# FPGA.net
KiCad netlist of a schematic drawn in Altium Designer
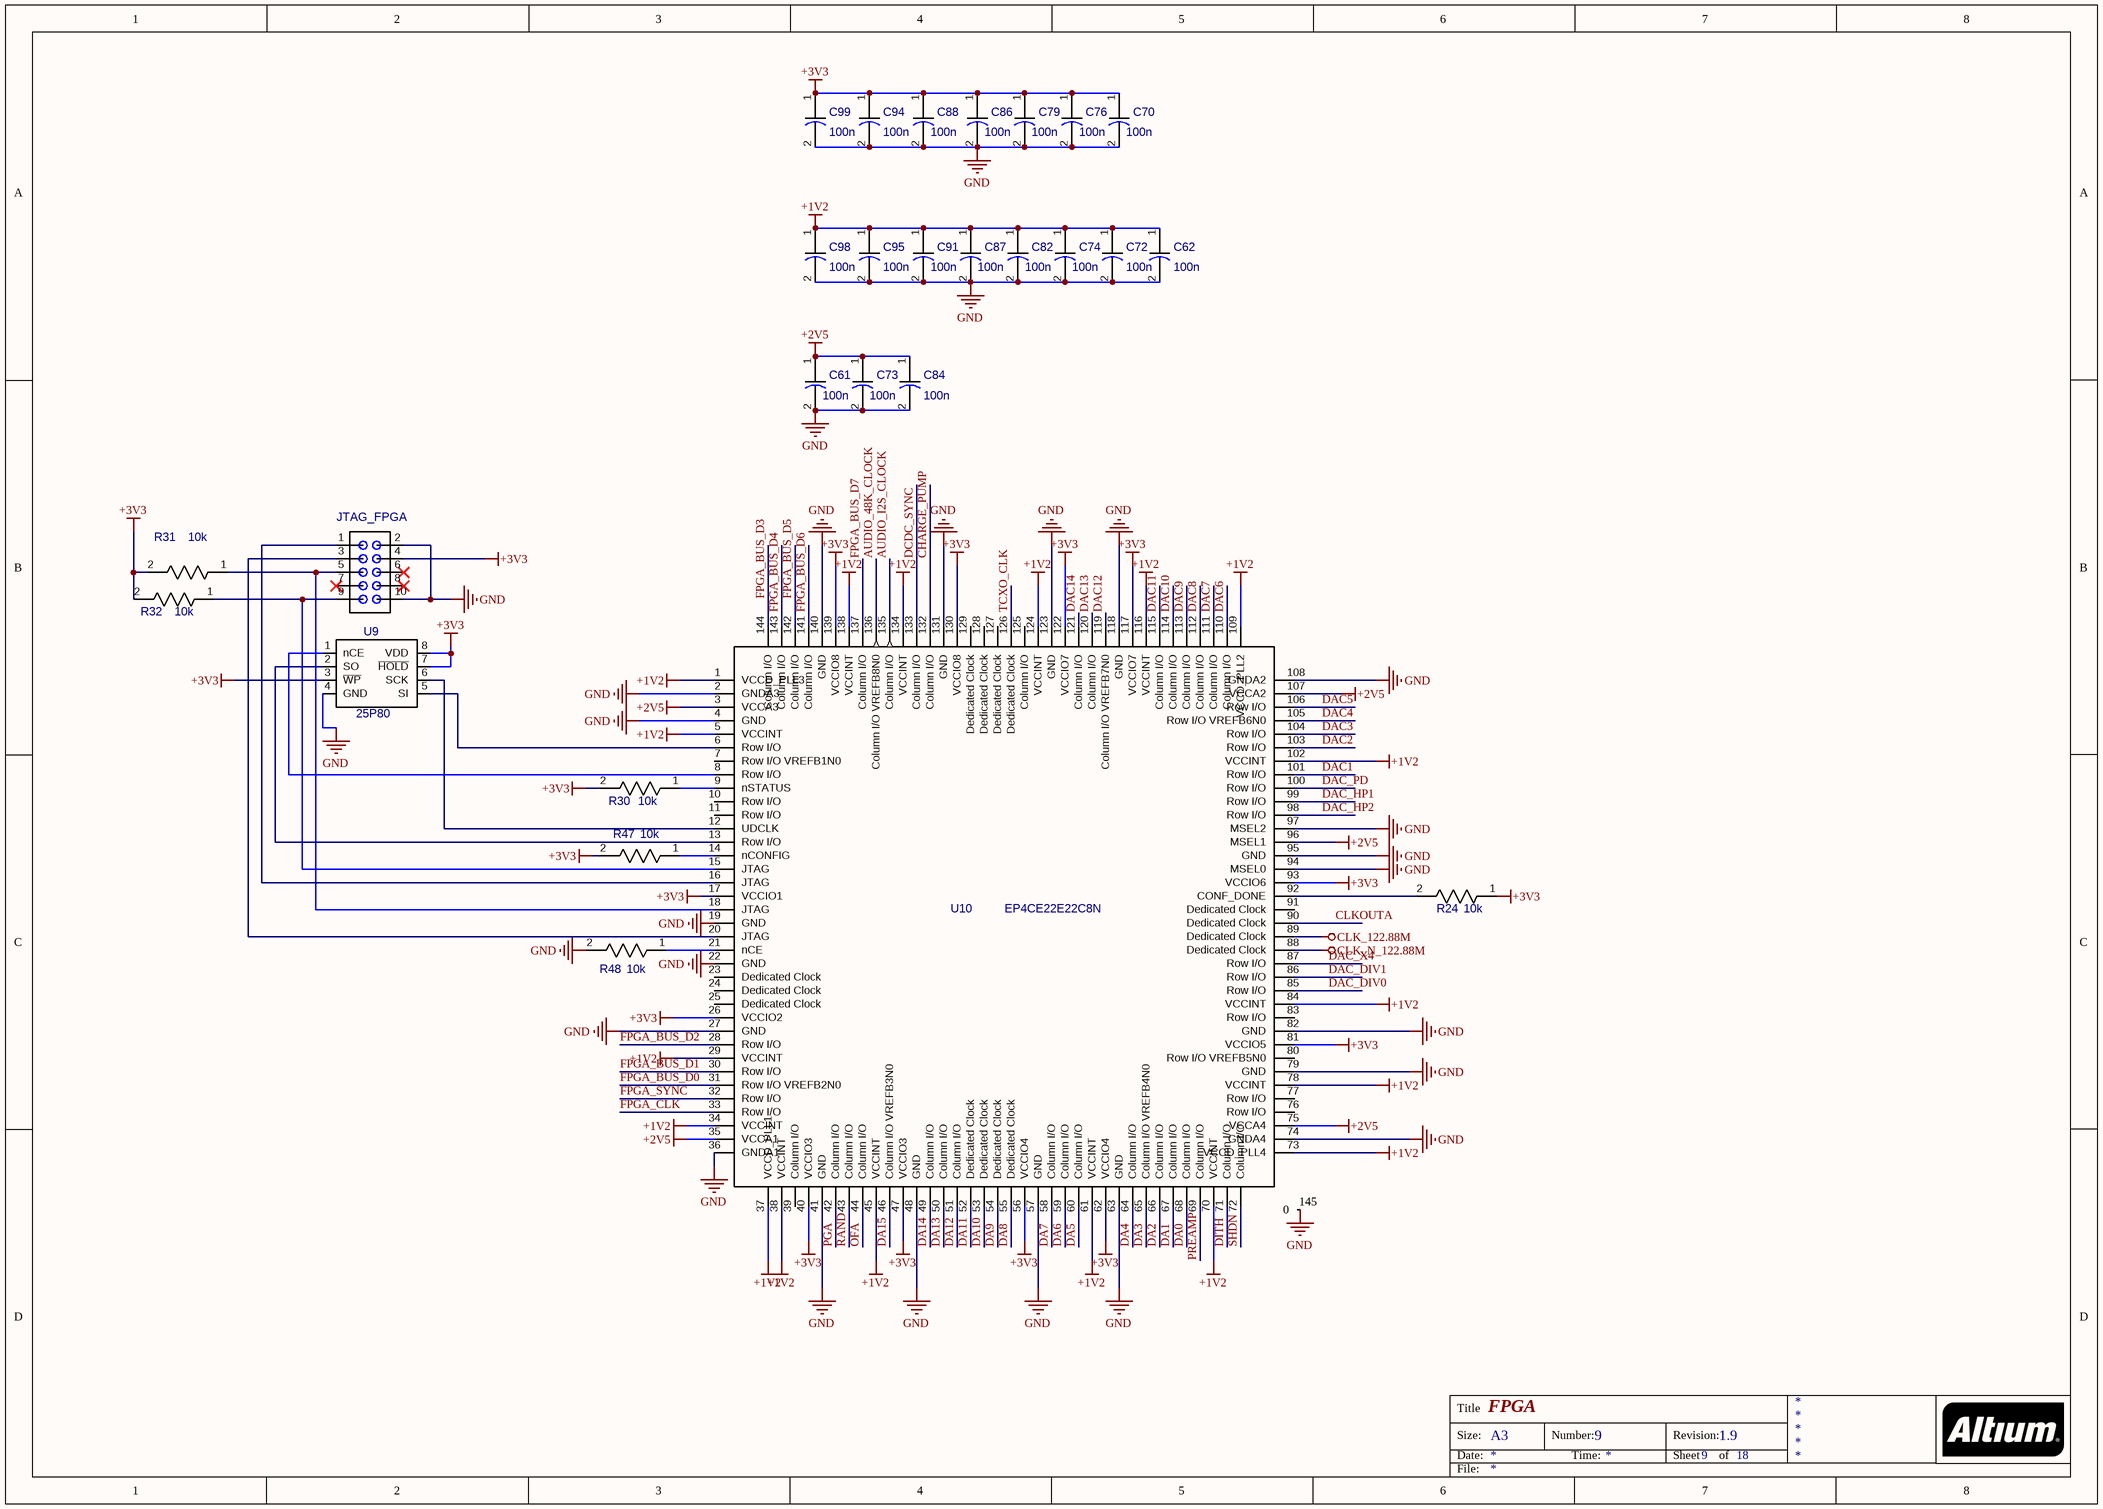
[diagram p0: FPGA.SchDoc]

(export (version "E")
  (design (tool "Eeschema 10.0.6"))
  (components
    (comp (ref "C61")
      (value "100n")
      (footprint "CAP_0805")
      (description "CAP_0805")
      (libsource (lib "*") (part "CAP_0805"))
    )
    (comp (ref "C62")
      (value "100n")
      (footprint "CAP_0805")
      (description "CAP_0805")
      (libsource (lib "*") (part "CAP_0805"))
    )
    (comp (ref "C70")
      (value "100n")
      (footprint "CAP_0805")
      (description "CAP_0805")
      (libsource (lib "*") (part "CAP_0805"))
    )
    (comp (ref "C72")
      (value "100n")
      (footprint "CAP_0805")
      (description "CAP_0805")
      (libsource (lib "*") (part "CAP_0805"))
    )
    (comp (ref "C73")
      (value "100n")
      (footprint "CAP_0805")
      (description "CAP_0805")
      (libsource (lib "*") (part "CAP_0805"))
    )
    (comp (ref "C74")
      (value "100n")
      (footprint "CAP_0805")
      (description "CAP_0805")
      (libsource (lib "*") (part "CAP_0805"))
    )
    (comp (ref "C76")
      (value "100n")
      (footprint "CAP_0805")
      (description "CAP_0805")
      (libsource (lib "*") (part "CAP_0805"))
    )
    (comp (ref "C79")
      (value "100n")
      (footprint "CAP_0805")
      (description "CAP_0805")
      (libsource (lib "*") (part "CAP_0805"))
    )
    (comp (ref "C82")
      (value "100n")
      (footprint "CAP_0805")
      (description "CAP_0805")
      (libsource (lib "*") (part "CAP_0805"))
    )
    (comp (ref "C84")
      (value "100n")
      (footprint "CAP_0805")
      (description "CAP_0805")
      (libsource (lib "*") (part "CAP_0805"))
    )
    (comp (ref "C86")
      (value "100n")
      (footprint "CAP_0805")
      (description "CAP_0805")
      (libsource (lib "*") (part "CAP_0805"))
    )
    (comp (ref "C87")
      (value "100n")
      (footprint "CAP_0805")
      (description "CAP_0805")
      (libsource (lib "*") (part "CAP_0805"))
    )
    (comp (ref "C88")
      (value "100n")
      (footprint "CAP_0805")
      (description "CAP_0805")
      (libsource (lib "*") (part "CAP_0805"))
    )
    (comp (ref "C91")
      (value "100n")
      (footprint "CAP_0805")
      (description "CAP_0805")
      (libsource (lib "*") (part "CAP_0805"))
    )
    (comp (ref "C94")
      (value "100n")
      (footprint "CAP_0805")
      (description "CAP_0805")
      (libsource (lib "*") (part "CAP_0805"))
    )
    (comp (ref "C95")
      (value "100n")
      (footprint "CAP_0805")
      (description "CAP_0805")
      (libsource (lib "*") (part "CAP_0805"))
    )
    (comp (ref "C98")
      (value "100n")
      (footprint "CAP_0805")
      (description "CAP_0805")
      (libsource (lib "*") (part "CAP_0805"))
    )
    (comp (ref "C99")
      (value "100n")
      (footprint "CAP_0805")
      (description "CAP_0805")
      (libsource (lib "*") (part "CAP_0805"))
    )
    (comp (ref "JTAG_FPGA")
      (value "~")
      (footprint "IDC10")
      (description "IDC10")
      (libsource (lib "*") (part "IDC10"))
    )
    (comp (ref "R24")
      (value "10k")
      (footprint "RES_0805")
      (description "RES_0805")
      (libsource (lib "*") (part "RES_0805"))
    )
    (comp (ref "R30")
      (value "10k")
      (footprint "RES_0805")
      (description "RES_0805")
      (libsource (lib "*") (part "RES_0805"))
    )
    (comp (ref "R31")
      (value "10k")
      (footprint "RES_0805")
      (description "RES_0805")
      (libsource (lib "*") (part "RES_0805"))
    )
    (comp (ref "R32")
      (value "10k")
      (footprint "RES_0805")
      (description "RES_0805")
      (libsource (lib "*") (part "RES_0805"))
    )
    (comp (ref "R47")
      (value "10k")
      (footprint "RES_0805")
      (description "RES_0805")
      (libsource (lib "*") (part "RES_0805"))
    )
    (comp (ref "R48")
      (value "10k")
      (footprint "RES_0805")
      (description "RES_0805")
      (libsource (lib "*") (part "RES_0805"))
    )
    (comp (ref "U9") (value "25P80") (footprint "25P80") (libsource (lib "*") (part "25P80")))
    (comp (ref "U10")
      (value "EP4CE22E22C8N")
      (footprint "QFP144-20-2222A")
      (libsource (lib "*") (part "EP4CE22E22C8N"))
    )
  )
  (nets
    (net (code "1") (name "+1V2") (class "Default")
      (node (ref "C62") (pin "1") (pinfunction "1_1") (pintype "passive"))
      (node (ref "C72") (pin "1") (pinfunction "1_1") (pintype "passive"))
      (node (ref "C74") (pin "1") (pinfunction "1_1") (pintype "passive"))
      (node (ref "C82") (pin "1") (pinfunction "1_1") (pintype "passive"))
      (node (ref "C87") (pin "1") (pinfunction "1_1") (pintype "passive"))
      (node (ref "C91") (pin "1") (pinfunction "1_1") (pintype "passive"))
      (node (ref "C95") (pin "1") (pinfunction "1_1") (pintype "passive"))
      (node (ref "C98") (pin "1") (pinfunction "1_1") (pintype "passive"))
      (node (ref "U10") (pin "1") (pinfunction "VCCD_PLL3_1") (pintype "passive"))
      (node (ref "U10") (pin "102") (pinfunction "VCCINT_102") (pintype "passive"))
      (node (ref "U10") (pin "109") (pinfunction "VCCD_PLL2_109") (pintype "passive"))
      (node (ref "U10") (pin "116") (pinfunction "VCCINT_116") (pintype "passive"))
      (node (ref "U10") (pin "124") (pinfunction "VCCINT_124") (pintype "passive"))
      (node (ref "U10") (pin "134") (pinfunction "VCCINT_134") (pintype "passive"))
      (node (ref "U10") (pin "138") (pinfunction "VCCINT_138") (pintype "passive"))
      (node (ref "U10") (pin "29") (pinfunction "VCCINT_29") (pintype "passive"))
      (node (ref "U10") (pin "34") (pinfunction "VCCINT_34") (pintype "passive"))
      (node (ref "U10") (pin "37") (pinfunction "VCCD_PLL1_37") (pintype "passive"))
      (node (ref "U10") (pin "38") (pinfunction "VCCINT_38") (pintype "passive"))
      (node (ref "U10") (pin "45") (pinfunction "VCCINT_45") (pintype "passive"))
      (node (ref "U10") (pin "5") (pinfunction "VCCINT_5") (pintype "passive"))
      (node (ref "U10") (pin "61") (pinfunction "VCCINT_61") (pintype "passive"))
      (node (ref "U10") (pin "70") (pinfunction "VCCINT_70") (pintype "passive"))
      (node (ref "U10") (pin "73") (pinfunction "VCCD_PLL4_73") (pintype "passive"))
      (node (ref "U10") (pin "78") (pinfunction "VCCINT_78") (pintype "passive"))
      (node (ref "U10") (pin "84") (pinfunction "VCCINT_84") (pintype "passive"))
    )
    (net (code "2") (name "+2V5") (class "Default")
      (node (ref "C61") (pin "1") (pinfunction "1_1") (pintype "passive"))
      (node (ref "C73") (pin "1") (pinfunction "1_1") (pintype "passive"))
      (node (ref "C84") (pin "1") (pinfunction "1_1") (pintype "passive"))
      (node (ref "U10") (pin "107") (pinfunction "VCCA2_107") (pintype "passive"))
      (node (ref "U10") (pin "3") (pinfunction "VCCA3_3") (pintype "passive"))
      (node (ref "U10") (pin "35") (pinfunction "VCCA1_35") (pintype "passive"))
      (node (ref "U10") (pin "75") (pinfunction "VCCA4_75") (pintype "passive"))
      (node (ref "U10") (pin "96") (pinfunction "MSEL1_96") (pintype "passive"))
    )
    (net (code "3") (name "+3V3") (class "Default")
      (node (ref "C70") (pin "1") (pinfunction "1_1") (pintype "passive"))
      (node (ref "C76") (pin "1") (pinfunction "1_1") (pintype "passive"))
      (node (ref "C79") (pin "1") (pinfunction "1_1") (pintype "passive"))
      (node (ref "C86") (pin "1") (pinfunction "1_1") (pintype "passive"))
      (node (ref "C88") (pin "1") (pinfunction "1_1") (pintype "passive"))
      (node (ref "C94") (pin "1") (pinfunction "1_1") (pintype "passive"))
      (node (ref "C99") (pin "1") (pinfunction "1_1") (pintype "passive"))
      (node (ref "JTAG_FPGA") (pin "4") (pinfunction "4_4") (pintype "passive"))
      (node (ref "R24") (pin "1") (pinfunction "1_1") (pintype "passive"))
      (node (ref "R30") (pin "2") (pinfunction "2_2") (pintype "passive"))
      (node (ref "R31") (pin "2") (pinfunction "2_2") (pintype "passive"))
      (node (ref "R32") (pin "2") (pinfunction "2_2") (pintype "passive"))
      (node (ref "R47") (pin "2") (pinfunction "2_2") (pintype "passive"))
      (node (ref "U10") (pin "117") (pinfunction "VCCIO7_117") (pintype "passive"))
      (node (ref "U10") (pin "122") (pinfunction "VCCIO7_122") (pintype "passive"))
      (node (ref "U10") (pin "130") (pinfunction "VCCIO8_130") (pintype "passive"))
      (node (ref "U10") (pin "139") (pinfunction "VCCIO8_139") (pintype "passive"))
      (node (ref "U10") (pin "17") (pinfunction "VCCIO1_17") (pintype "passive"))
      (node (ref "U10") (pin "26") (pinfunction "VCCIO2_26") (pintype "passive"))
      (node (ref "U10") (pin "40") (pinfunction "VCCIO3_40") (pintype "passive"))
      (node (ref "U10") (pin "47") (pinfunction "VCCIO3_47") (pintype "passive"))
      (node (ref "U10") (pin "56") (pinfunction "VCCIO4_56") (pintype "passive"))
      (node (ref "U10") (pin "62") (pinfunction "VCCIO4_62") (pintype "passive"))
      (node (ref "U10") (pin "81") (pinfunction "VCCIO5_81") (pintype "passive"))
      (node (ref "U10") (pin "93") (pinfunction "VCCIO6_93") (pintype "passive"))
      (node (ref "U9") (pin "3") (pinfunction "~{WP}_3") (pintype "passive"))
      (node (ref "U9") (pin "7") (pinfunction "~{HOLD}_7") (pintype "passive"))
      (node (ref "U9") (pin "8") (pinfunction "VDD_8") (pintype "passive"))
    )
    (net (code "4") (name "/AUDIO_48K_CLOCK") (class "Default")
      (node (ref "U10") (pin "136") (pinfunction "Column_I/O_VREFB8N0_136") (pintype "output"))
    )
    (net (code "5") (name "/AUDIO_I2S_CLOCK") (class "Default")
      (node (ref "U10") (pin "135") (pinfunction "Column_I/O_135") (pintype "output"))
    )
    (net (code "6") (name "/CHARGE_PUMP") (class "Default")
      (node (ref "U10") (pin "132") (pinfunction "Column_I/O_132") (pintype "passive"))
    )
    (net (code "7") (name "/CLKOUTA") (class "Default")
      (node (ref "U10") (pin "90") (pinfunction "Dedicated_Clock_90") (pintype "passive"))
    )
    (net (code "8") (name "/DA0") (class "Default")
      (node (ref "U10") (pin "68") (pinfunction "Column_I/O_68") (pintype "passive"))
    )
    (net (code "9") (name "/DA1") (class "Default")
      (node (ref "U10") (pin "67") (pinfunction "Column_I/O_67") (pintype "passive"))
    )
    (net (code "10") (name "/DA2") (class "Default")
      (node (ref "U10") (pin "66") (pinfunction "Column_I/O_66") (pintype "passive"))
    )
    (net (code "11") (name "/DA3") (class "Default")
      (node (ref "U10") (pin "65") (pinfunction "Column_I/O_VREFB4N0_65") (pintype "passive"))
    )
    (net (code "12") (name "/DA4") (class "Default")
      (node (ref "U10") (pin "64") (pinfunction "Column_I/O_64") (pintype "passive"))
    )
    (net (code "13") (name "/DA5") (class "Default")
      (node (ref "U10") (pin "60") (pinfunction "Column_I/O_60") (pintype "passive"))
    )
    (net (code "14") (name "/DA6") (class "Default")
      (node (ref "U10") (pin "59") (pinfunction "Column_I/O_59") (pintype "passive"))
    )
    (net (code "15") (name "/DA7") (class "Default")
      (node (ref "U10") (pin "58") (pinfunction "Column_I/O_58") (pintype "passive"))
    )
    (net (code "16") (name "/DA8") (class "Default")
      (node (ref "U10") (pin "55") (pinfunction "Dedicated_Clock_55") (pintype "passive"))
    )
    (net (code "17") (name "/DA9") (class "Default")
      (node (ref "U10") (pin "54") (pinfunction "Dedicated_Clock_54") (pintype "passive"))
    )
    (net (code "18") (name "/DA10") (class "Default")
      (node (ref "U10") (pin "53") (pinfunction "Dedicated_Clock_53") (pintype "passive"))
    )
    (net (code "19") (name "/DA11") (class "Default")
      (node (ref "U10") (pin "52") (pinfunction "Dedicated_Clock_52") (pintype "passive"))
    )
    (net (code "20") (name "/DA12") (class "Default")
      (node (ref "U10") (pin "51") (pinfunction "Column_I/O_51") (pintype "passive"))
    )
    (net (code "21") (name "/DA13") (class "Default")
      (node (ref "U10") (pin "50") (pinfunction "Column_I/O_50") (pintype "passive"))
    )
    (net (code "22") (name "/DA14") (class "Default")
      (node (ref "U10") (pin "49") (pinfunction "Column_I/O_49") (pintype "passive"))
    )
    (net (code "23") (name "/DA15") (class "Default")
      (node (ref "U10") (pin "46") (pinfunction "Column_I/O_VREFB3N0_46") (pintype "passive"))
    )
    (net (code "24") (name "/DAC1") (class "Default")
      (node (ref "U10") (pin "101") (pinfunction "Row_I/O_101") (pintype "passive"))
    )
    (net (code "25") (name "/DAC2") (class "Default")
      (node (ref "U10") (pin "103") (pinfunction "Row_I/O_103") (pintype "passive"))
    )
    (net (code "26") (name "/DAC3") (class "Default")
      (node (ref "U10") (pin "104") (pinfunction "Row_I/O_104") (pintype "passive"))
    )
    (net (code "27") (name "/DAC4") (class "Default")
      (node (ref "U10") (pin "105") (pinfunction "Row_I/O_VREFB6N0_105") (pintype "passive"))
    )
    (net (code "28") (name "/DAC5") (class "Default")
      (node (ref "U10") (pin "106") (pinfunction "Row_I/O_106") (pintype "passive"))
    )
    (net (code "29") (name "/DAC6") (class "Default")
      (node (ref "U10") (pin "110") (pinfunction "Column_I/O_110") (pintype "passive"))
    )
    (net (code "30") (name "/DAC7") (class "Default")
      (node (ref "U10") (pin "111") (pinfunction "Column_I/O_111") (pintype "passive"))
    )
    (net (code "31") (name "/DAC8") (class "Default")
      (node (ref "U10") (pin "112") (pinfunction "Column_I/O_112") (pintype "passive"))
    )
    (net (code "32") (name "/DAC9") (class "Default")
      (node (ref "U10") (pin "113") (pinfunction "Column_I/O_113") (pintype "passive"))
    )
    (net (code "33") (name "/DAC10") (class "Default")
      (node (ref "U10") (pin "114") (pinfunction "Column_I/O_114") (pintype "passive"))
    )
    (net (code "34") (name "/DAC11") (class "Default")
      (node (ref "U10") (pin "115") (pinfunction "Column_I/O_115") (pintype "passive"))
    )
    (net (code "35") (name "/DAC12") (class "Default")
      (node (ref "U10") (pin "119") (pinfunction "Column_I/O_VREFB7N0_119") (pintype "passive"))
    )
    (net (code "36") (name "/DAC13") (class "Default")
      (node (ref "U10") (pin "120") (pinfunction "Column_I/O_120") (pintype "passive"))
    )
    (net (code "37") (name "/DAC14") (class "Default")
      (node (ref "U10") (pin "121") (pinfunction "Column_I/O_121") (pintype "passive"))
    )
    (net (code "38") (name "/DAC_DIV0") (class "Default")
      (node (ref "U10") (pin "85") (pinfunction "Row_I/O_85") (pintype "passive"))
    )
    (net (code "39") (name "/DAC_DIV1") (class "Default")
      (node (ref "U10") (pin "86") (pinfunction "Row_I/O_86") (pintype "passive"))
    )
    (net (code "40") (name "/DAC_HP1") (class "Default")
      (node (ref "U10") (pin "99") (pinfunction "Row_I/O_99") (pintype "passive"))
    )
    (net (code "41") (name "/DAC_HP2") (class "Default")
      (node (ref "U10") (pin "98") (pinfunction "Row_I/O_98") (pintype "passive"))
    )
    (net (code "42") (name "/DAC_PD") (class "Default")
      (node (ref "U10") (pin "100") (pinfunction "Row_I/O_100") (pintype "passive"))
    )
    (net (code "43") (name "/DAC_X4") (class "Default")
      (node (ref "U10") (pin "87") (pinfunction "Row_I/O_87") (pintype "passive"))
    )
    (net (code "44") (name "/DCDC_SYNC") (class "Default")
      (node (ref "U10") (pin "133") (pinfunction "Column_I/O_133") (pintype "passive"))
    )
    (net (code "45") (name "/DITH") (class "Default")
      (node (ref "U10") (pin "71") (pinfunction "Column_I/O_71") (pintype "passive"))
    )
    (net (code "46") (name "/FPGA_BUS_D0") (class "Default")
      (node (ref "U10") (pin "31") (pinfunction "Row_I/O_VREFB2N0_31") (pintype "passive"))
    )
    (net (code "47") (name "/FPGA_BUS_D1") (class "Default")
      (node (ref "U10") (pin "30") (pinfunction "Row_I/O_30") (pintype "passive"))
    )
    (net (code "48") (name "/FPGA_BUS_D2") (class "Default")
      (node (ref "U10") (pin "28") (pinfunction "Row_I/O_28") (pintype "passive"))
    )
    (net (code "49") (name "/FPGA_BUS_D3") (class "Default")
      (node (ref "U10") (pin "144") (pinfunction "Column_I/O_144") (pintype "passive"))
    )
    (net (code "50") (name "/FPGA_BUS_D4") (class "Default")
      (node (ref "U10") (pin "143") (pinfunction "Column_I/O_143") (pintype "passive"))
    )
    (net (code "51") (name "/FPGA_BUS_D5") (class "Default")
      (node (ref "U10") (pin "142") (pinfunction "Column_I/O_142") (pintype "passive"))
    )
    (net (code "52") (name "/FPGA_BUS_D6") (class "Default")
      (node (ref "U10") (pin "141") (pinfunction "Column_I/O_141") (pintype "passive"))
    )
    (net (code "53") (name "/FPGA_BUS_D7") (class "Default")
      (node (ref "U10") (pin "137") (pinfunction "Column_I/O_137") (pintype "passive"))
    )
    (net (code "54") (name "/FPGA_CLK") (class "Default")
      (node (ref "U10") (pin "33") (pinfunction "Row_I/O_33") (pintype "passive"))
    )
    (net (code "55") (name "/FPGA_SYNC") (class "Default")
      (node (ref "U10") (pin "32") (pinfunction "Row_I/O_32") (pintype "passive"))
    )
    (net (code "56") (name "/OFA") (class "Default")
      (node (ref "U10") (pin "44") (pinfunction "Column_I/O_44") (pintype "passive"))
    )
    (net (code "57") (name "/PGA") (class "Default")
      (node (ref "U10") (pin "42") (pinfunction "Column_I/O_42") (pintype "passive"))
    )
    (net (code "58") (name "/PREAMP") (class "Default")
      (node (ref "U10") (pin "69") (pinfunction "Column_I/O_69") (pintype "passive"))
    )
    (net (code "59") (name "/RAND") (class "Default")
      (node (ref "U10") (pin "43") (pinfunction "Column_I/O_43") (pintype "passive"))
    )
    (net (code "60") (name "/SHDN") (class "Default")
      (node (ref "U10") (pin "72") (pinfunction "Column_I/O_72") (pintype "passive"))
    )
    (net (code "61") (name "/TCXO_CLK") (class "Default")
      (node (ref "U10") (pin "126") (pinfunction "Dedicated_Clock_126") (pintype "passive"))
    )
    (net (code "62") (name "CLK_122.88M") (class "Default")
      (node (ref "U10") (pin "89") (pinfunction "Dedicated_Clock_89") (pintype "passive"))
    )
    (net (code "63") (name "CLK_N_122.88M") (class "Default")
      (node (ref "U10") (pin "88") (pinfunction "Dedicated_Clock_88") (pintype "passive"))
    )
    (net (code "64") (name "GND") (class "Default")
      (node (ref "C61") (pin "2") (pinfunction "2_2") (pintype "passive"))
      (node (ref "C62") (pin "2") (pinfunction "2_2") (pintype "passive"))
      (node (ref "C70") (pin "2") (pinfunction "2_2") (pintype "passive"))
      (node (ref "C72") (pin "2") (pinfunction "2_2") (pintype "passive"))
      (node (ref "C73") (pin "2") (pinfunction "2_2") (pintype "passive"))
      (node (ref "C74") (pin "2") (pinfunction "2_2") (pintype "passive"))
      (node (ref "C76") (pin "2") (pinfunction "2_2") (pintype "passive"))
      (node (ref "C79") (pin "2") (pinfunction "2_2") (pintype "passive"))
      (node (ref "C82") (pin "2") (pinfunction "2_2") (pintype "passive"))
      (node (ref "C84") (pin "2") (pinfunction "2_2") (pintype "passive"))
      (node (ref "C86") (pin "2") (pinfunction "2_2") (pintype "passive"))
      (node (ref "C87") (pin "2") (pinfunction "2_2") (pintype "passive"))
      (node (ref "C88") (pin "2") (pinfunction "2_2") (pintype "passive"))
      (node (ref "C91") (pin "2") (pinfunction "2_2") (pintype "passive"))
      (node (ref "C94") (pin "2") (pinfunction "2_2") (pintype "passive"))
      (node (ref "C95") (pin "2") (pinfunction "2_2") (pintype "passive"))
      (node (ref "C98") (pin "2") (pinfunction "2_2") (pintype "passive"))
      (node (ref "C99") (pin "2") (pinfunction "2_2") (pintype "passive"))
      (node (ref "JTAG_FPGA") (pin "10") (pinfunction "10_10") (pintype "passive"))
      (node (ref "JTAG_FPGA") (pin "2") (pinfunction "2_2") (pintype "passive"))
      (node (ref "R48") (pin "2") (pinfunction "2_2") (pintype "passive"))
      (node (ref "U10") (pin "108") (pinfunction "GNDA2_108") (pintype "passive"))
      (node (ref "U10") (pin "118") (pinfunction "GND_118") (pintype "passive"))
      (node (ref "U10") (pin "123") (pinfunction "GND_123") (pintype "passive"))
      (node (ref "U10") (pin "131") (pinfunction "GND_131") (pintype "passive"))
      (node (ref "U10") (pin "140") (pinfunction "GND_140") (pintype "passive"))
      (node (ref "U10") (pin "145") (pinfunction "0_145") (pintype "passive"))
      (node (ref "U10") (pin "19") (pinfunction "GND_19") (pintype "passive"))
      (node (ref "U10") (pin "2") (pinfunction "GNDA3_2") (pintype "passive"))
      (node (ref "U10") (pin "22") (pinfunction "GND_22") (pintype "passive"))
      (node (ref "U10") (pin "27") (pinfunction "GND_27") (pintype "passive"))
      (node (ref "U10") (pin "36") (pinfunction "GNDA1_36") (pintype "passive"))
      (node (ref "U10") (pin "4") (pinfunction "GND_4") (pintype "passive"))
      (node (ref "U10") (pin "41") (pinfunction "GND_41") (pintype "passive"))
      (node (ref "U10") (pin "48") (pinfunction "GND_48") (pintype "passive"))
      (node (ref "U10") (pin "57") (pinfunction "GND_57") (pintype "passive"))
      (node (ref "U10") (pin "63") (pinfunction "GND_63") (pintype "passive"))
      (node (ref "U10") (pin "74") (pinfunction "GNDA4_74") (pintype "passive"))
      (node (ref "U10") (pin "79") (pinfunction "GND_79") (pintype "passive"))
      (node (ref "U10") (pin "82") (pinfunction "GND_82") (pintype "passive"))
      (node (ref "U10") (pin "94") (pinfunction "MSEL0_94") (pintype "passive"))
      (node (ref "U10") (pin "95") (pinfunction "GND_95") (pintype "passive"))
      (node (ref "U10") (pin "97") (pinfunction "MSEL2_97") (pintype "passive"))
      (node (ref "U9") (pin "4") (pinfunction "GND_4") (pintype "passive"))
    )
    (net (code "65") (name "Net-(JTAG_FPGA-Pad1)") (class "Default")
      (node (ref "JTAG_FPGA") (pin "1") (pinfunction "1_1") (pintype "passive"))
      (node (ref "U10") (pin "16") (pinfunction "JTAG_16") (pintype "passive"))
    )
    (net (code "66") (name "Net-(JTAG_FPGA-Pad3)") (class "Default")
      (node (ref "JTAG_FPGA") (pin "3") (pinfunction "3_3") (pintype "passive"))
      (node (ref "U10") (pin "20") (pinfunction "JTAG_20") (pintype "passive"))
    )
    (net (code "67") (name "Net-(JTAG_FPGA-Pad5)") (class "Default")
      (node (ref "JTAG_FPGA") (pin "5") (pinfunction "5_5") (pintype "passive"))
      (node (ref "R31") (pin "1") (pinfunction "1_1") (pintype "passive"))
      (node (ref "U10") (pin "18") (pinfunction "JTAG_18") (pintype "passive"))
    )
    (net (code "68") (name "Net-(JTAG_FPGA-Pad9)") (class "Default")
      (node (ref "JTAG_FPGA") (pin "9") (pinfunction "9_9") (pintype "passive"))
      (node (ref "R32") (pin "1") (pinfunction "1_1") (pintype "passive"))
      (node (ref "U10") (pin "15") (pinfunction "JTAG_15") (pintype "passive"))
    )
    (net (code "69") (name "Net-(U9-SI)") (class "Default")
      (node (ref "U10") (pin "6") (pinfunction "Row_I/O_6") (pintype "passive"))
      (node (ref "U9") (pin "5") (pinfunction "SI_5") (pintype "passive"))
    )
    (net (code "70") (name "Net-(U9-SO)") (class "Default")
      (node (ref "U10") (pin "13") (pinfunction "Row_I/O_13") (pintype "passive"))
      (node (ref "U9") (pin "2") (pinfunction "SO_2") (pintype "passive"))
    )
    (net (code "71") (name "Net-(U9-nCE)") (class "Default")
      (node (ref "U10") (pin "8") (pinfunction "Row_I/O_8") (pintype "passive"))
      (node (ref "U9") (pin "1") (pinfunction "nCE_1") (pintype "passive"))
    )
    (net (code "72") (name "Net-(U10-CONF_DONE)") (class "Default")
      (node (ref "R24") (pin "2") (pinfunction "2_2") (pintype "passive"))
      (node (ref "U10") (pin "92") (pinfunction "CONF_DONE_92") (pintype "passive"))
    )
    (net (code "73") (name "Net-(U10-UDCLK)") (class "Default")
      (node (ref "U10") (pin "12") (pinfunction "UDCLK_12") (pintype "passive"))
      (node (ref "U9") (pin "6") (pinfunction "SCK_6") (pintype "passive"))
    )
    (net (code "74") (name "Net-(U10-nCE)") (class "Default")
      (node (ref "R48") (pin "1") (pinfunction "1_1") (pintype "passive"))
      (node (ref "U10") (pin "21") (pinfunction "nCE_21") (pintype "passive"))
    )
    (net (code "75") (name "Net-(U10-nCONFIG)") (class "Default")
      (node (ref "R47") (pin "1") (pinfunction "1_1") (pintype "passive"))
      (node (ref "U10") (pin "14") (pinfunction "nCONFIG_14") (pintype "passive"))
    )
    (net (code "76") (name "Net-(U10-nSTATUS)") (class "Default")
      (node (ref "R30") (pin "1") (pinfunction "1_1") (pintype "passive"))
      (node (ref "U10") (pin "9") (pinfunction "nSTATUS_9") (pintype "passive"))
    )
    (net (code "77") (name "unconnected-(JTAG_FPGA-Pad6)") (class "Default")
      (node (ref "JTAG_FPGA") (pin "6") (pinfunction "6_6") (pintype "passive+no_connect"))
    )
    (net (code "78") (name "unconnected-(JTAG_FPGA-Pad7)") (class "Default")
      (node (ref "JTAG_FPGA") (pin "7") (pinfunction "7_7") (pintype "passive+no_connect"))
    )
    (net (code "79") (name "unconnected-(JTAG_FPGA-Pad8)") (class "Default")
      (node (ref "JTAG_FPGA") (pin "8") (pinfunction "8_8") (pintype "passive+no_connect"))
    )
    (net (code "80") (name "unconnected-(U10-Column_I{slash}O-Pad39)") (class "Default")
      (node (ref "U10") (pin "39") (pinfunction "Column_I/O_39") (pintype "passive"))
    )
    (net (code "81") (name "unconnected-(U10-Column_I{slash}O-Pad125)") (class "Default")
      (node (ref "U10") (pin "125") (pinfunction "Column_I/O_125") (pintype "passive"))
    )
    (net (code "82") (name "unconnected-(U10-Dedicated_Clock-Pad23)") (class "Default")
      (node (ref "U10") (pin "23") (pinfunction "Dedicated_Clock_23") (pintype "passive"))
    )
    (net (code "83") (name "unconnected-(U10-Dedicated_Clock-Pad24)") (class "Default")
      (node (ref "U10") (pin "24") (pinfunction "Dedicated_Clock_24") (pintype "passive"))
    )
    (net (code "84") (name "unconnected-(U10-Dedicated_Clock-Pad25)") (class "Default")
      (node (ref "U10") (pin "25") (pinfunction "Dedicated_Clock_25") (pintype "passive"))
    )
    (net (code "85") (name "unconnected-(U10-Dedicated_Clock-Pad91)") (class "Default")
      (node (ref "U10") (pin "91") (pinfunction "Dedicated_Clock_91") (pintype "passive"))
    )
    (net (code "86") (name "unconnected-(U10-Dedicated_Clock-Pad127)") (class "Default")
      (node (ref "U10") (pin "127") (pinfunction "Dedicated_Clock_127") (pintype "passive"))
    )
    (net (code "87") (name "unconnected-(U10-Dedicated_Clock-Pad128)") (class "Default")
      (node (ref "U10") (pin "128") (pinfunction "Dedicated_Clock_128") (pintype "passive"))
    )
    (net (code "88") (name "unconnected-(U10-Dedicated_Clock-Pad129)") (class "Default")
      (node (ref "U10") (pin "129") (pinfunction "Dedicated_Clock_129") (pintype "passive"))
    )
    (net (code "89") (name "unconnected-(U10-Row_I{slash}O-Pad10)") (class "Default")
      (node (ref "U10") (pin "10") (pinfunction "Row_I/O_10") (pintype "passive"))
    )
    (net (code "90") (name "unconnected-(U10-Row_I{slash}O-Pad11)") (class "Default")
      (node (ref "U10") (pin "11") (pinfunction "Row_I/O_11") (pintype "passive"))
    )
    (net (code "91") (name "unconnected-(U10-Row_I{slash}O-Pad76)") (class "Default")
      (node (ref "U10") (pin "76") (pinfunction "Row_I/O_76") (pintype "passive"))
    )
    (net (code "92") (name "unconnected-(U10-Row_I{slash}O-Pad77)") (class "Default")
      (node (ref "U10") (pin "77") (pinfunction "Row_I/O_77") (pintype "passive"))
    )
    (net (code "93") (name "unconnected-(U10-Row_I{slash}O-Pad83)") (class "Default")
      (node (ref "U10") (pin "83") (pinfunction "Row_I/O_83") (pintype "passive"))
    )
    (net (code "94") (name "unconnected-(U10-Row_I{slash}O_VREFB1N0-Pad7)") (class "Default")
      (node (ref "U10") (pin "7") (pinfunction "Row_I/O_VREFB1N0_7") (pintype "passive"))
    )
    (net (code "95") (name "unconnected-(U10-Row_I{slash}O_VREFB5N0-Pad80)") (class "Default")
      (node (ref "U10") (pin "80") (pinfunction "Row_I/O_VREFB5N0_80") (pintype "passive"))
    )
  )
)
